# blinkenrocket_cr2032.net
KiCad netlist of a schematic drawn in EAGLE
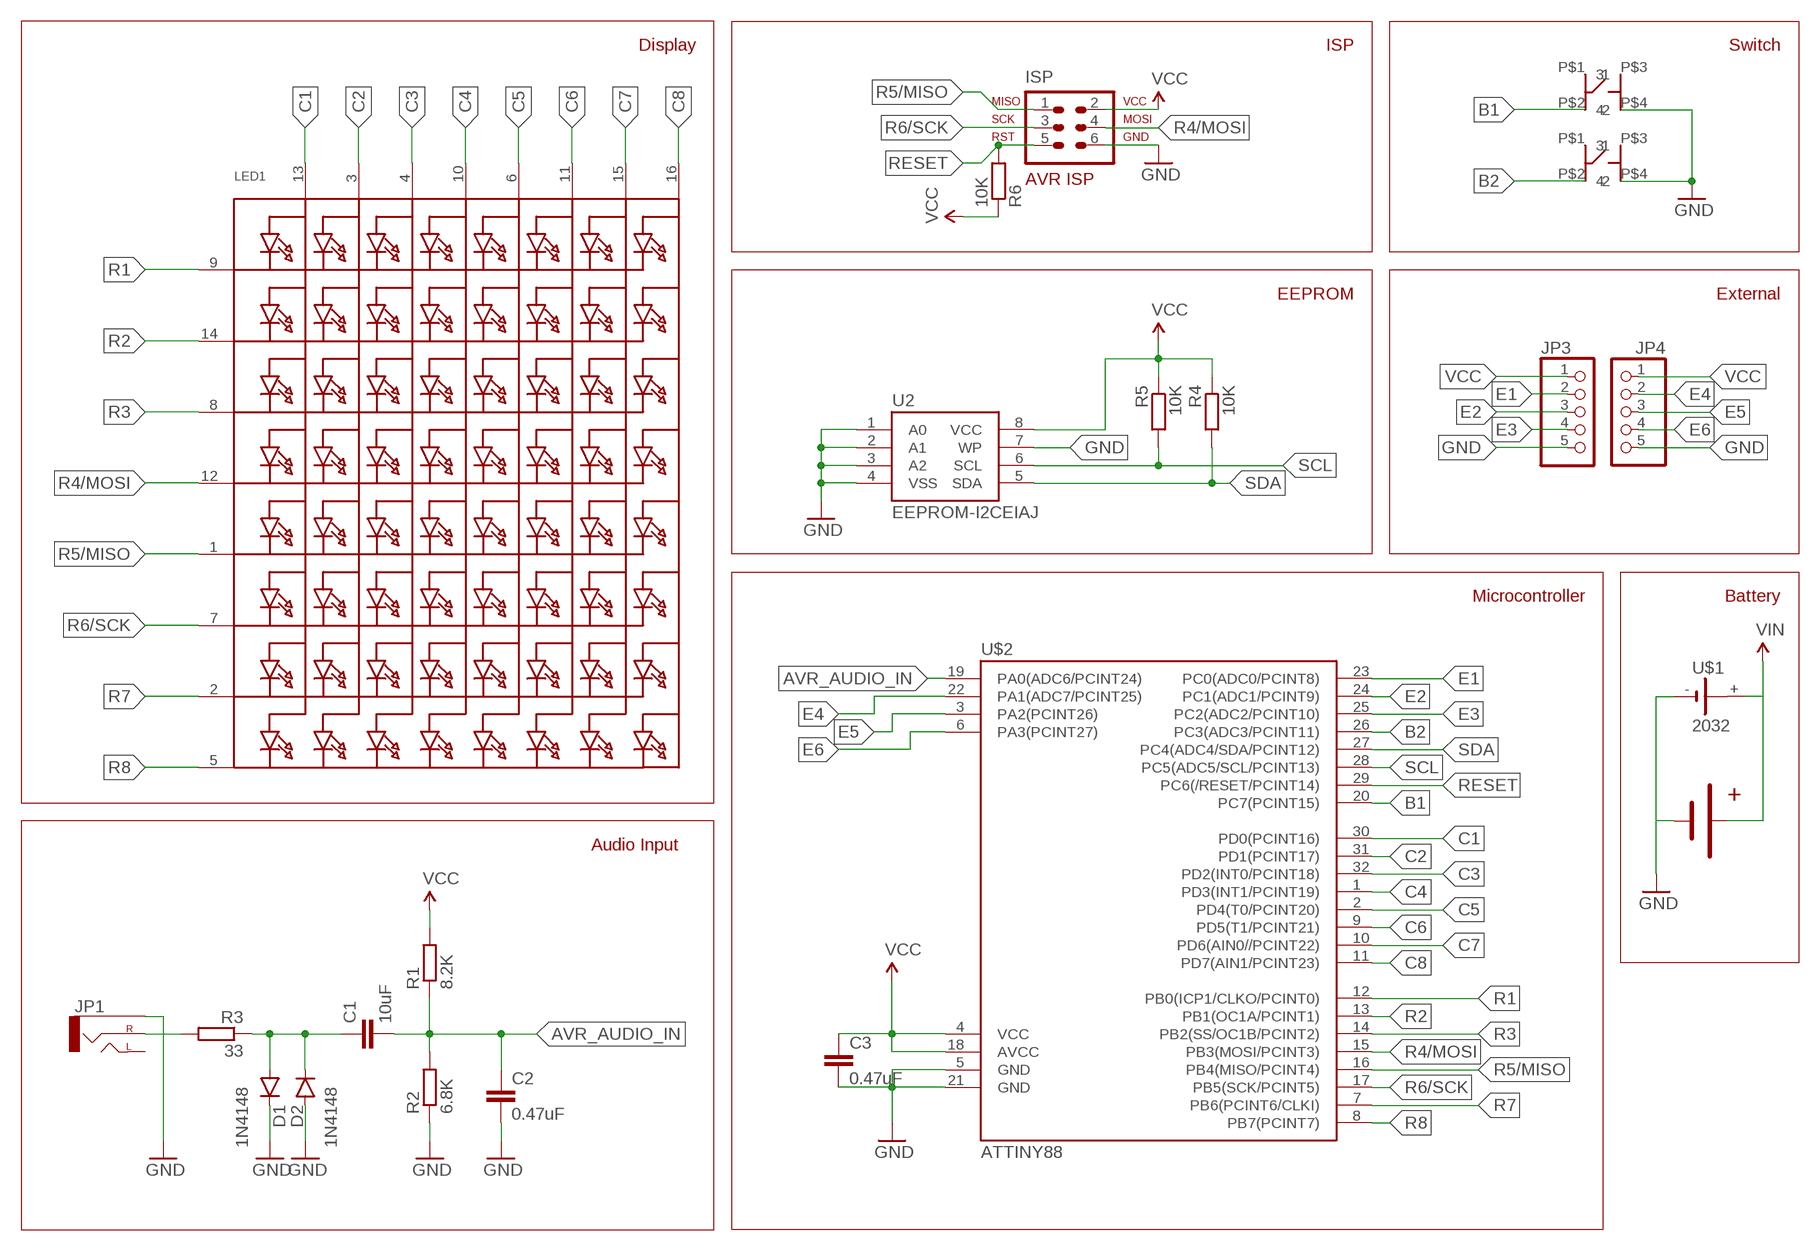
[diagram p0: schematic, sheet 1]

(export (version "E")
  (design (tool "Eeschema 10.0.6"))
  (components
    (comp (ref "C1")
      (value "10uF")
      (footprint "eagle-import:C0805K")
      (libsource (lib "eagle-import") (part "C-EUC0805K"))
    )
    (comp (ref "C2")
      (value "0.47uF")
      (footprint "eagle-import:C0805K")
      (libsource (lib "eagle-import") (part "C-EUC0805K"))
    )
    (comp (ref "C3")
      (value "0.47uF")
      (footprint "eagle-import:C0805K")
      (libsource (lib "eagle-import") (part "C-EUC0805K"))
    )
    (comp (ref "D1")
      (value "1N4148")
      (footprint "eagle-import:SOD-323")
      (libsource (lib "eagle-import") (part "DIODESOD"))
    )
    (comp (ref "D2")
      (value "1N4148")
      (footprint "eagle-import:SOD-323")
      (libsource (lib "eagle-import") (part "DIODESOD"))
    )
    (comp (ref "ISP")
      (value "AVR-ISP-6VERT")
      (footprint "eagle-import:AVR-ISP-6")
      (libsource (lib "eagle-import") (part "AVR-ISP-6VERT"))
    )
    (comp (ref "JP1")
      (value "AUDIO-JACKPTH")
      (footprint "eagle-import:AUDIO-JACK")
      (libsource (lib "eagle-import") (part "AUDIO-JACKPTH"))
    )
    (comp (ref "JP3")
      (value "PINHD-1X05_2.54-S")
      (footprint "eagle-import:1X05-S")
      (libsource (lib "eagle-import") (part "PINHD-1X05_2.54-S"))
    )
    (comp (ref "JP4")
      (value "PINHD-1X05_2.54-S")
      (footprint "eagle-import:1X05-S")
      (libsource (lib "eagle-import") (part "PINHD-1X05_2.54-S"))
    )
    (comp (ref "LED1")
      (value "SEGMENT_8X8_ROWCATHODEM12A881UR")
      (footprint "eagle-import:SEGMENT_BL-M12A881UR")
      (libsource (lib "eagle-import") (part "SEGMENT_8X8_ROWCATHODEM12A881UR"))
    )
    (comp (ref "R1")
      (value "8.2K")
      (footprint "eagle-import:M0805")
      (libsource (lib "eagle-import") (part "R-EU_M0805"))
    )
    (comp (ref "R2")
      (value "6.8K")
      (footprint "eagle-import:M0805")
      (libsource (lib "eagle-import") (part "R-EU_M0805"))
    )
    (comp (ref "R3")
      (value "33")
      (footprint "eagle-import:M0805")
      (libsource (lib "eagle-import") (part "R-EU_M0805"))
    )
    (comp (ref "R4")
      (value "10K")
      (footprint "eagle-import:M0805")
      (libsource (lib "eagle-import") (part "R-EU_M0805"))
    )
    (comp (ref "R5")
      (value "10K")
      (footprint "eagle-import:M0805")
      (libsource (lib "eagle-import") (part "R-EU_M0805"))
    )
    (comp (ref "R6")
      (value "10K")
      (footprint "eagle-import:M0805")
      (libsource (lib "eagle-import") (part "R-EU_M0805"))
    )
    (comp (ref "SW1")
      (value "SWITCH-4POMRON-6-6-SWITCH")
      (footprint "eagle-import:4P-OMRON-6-6-SWITCH")
      (libsource (lib "eagle-import") (part "SWITCH-4POMRON-6-6-SWITCH"))
    )
    (comp (ref "SW2")
      (value "SWITCH-4POMRON-6-6-SWITCH")
      (footprint "eagle-import:4P-OMRON-6-6-SWITCH")
      (libsource (lib "eagle-import") (part "SWITCH-4POMRON-6-6-SWITCH"))
    )
    (comp (ref "U$1")
      (value "2032")
      (footprint "eagle-import:KZH20SMD")
      (libsource (lib "eagle-import") (part "2032"))
    )
    (comp (ref "U$2")
      (value "ATTINY88")
      (footprint "eagle-import:TQFP32-08")
      (libsource (lib "eagle-import") (part "TINY48/88B"))
    )
    (comp (ref "U$3")
      (value "BATTERYPAD")
      (footprint "eagle-import:BATTERYPAD")
      (libsource (lib "eagle-import") (part "BATTERYPAD"))
    )
    (comp (ref "U2")
      (value "EEPROM-I2CEIAJ")
      (footprint "eagle-import:SO08-EIAJ")
      (libsource (lib "eagle-import") (part "EEPROM-I2CEIAJ"))
    )
  )
  (nets
    (net (code "1") (name "AVR_AUDIO_IN") (class "Default")
      (node (ref "C1") (pin "2") (pinfunction "2_2") (pintype "passive"))
      (node (ref "C2") (pin "1") (pinfunction "1_1") (pintype "passive"))
      (node (ref "R1") (pin "1") (pinfunction "1_1") (pintype "passive"))
      (node (ref "R2") (pin "2") (pinfunction "2_2") (pintype "passive"))
      (node (ref "U$2") (pin "19") (pinfunction "PA0(ADC6/PCINT24)_19") (pintype "bidirectional"))
    )
    (net (code "2") (name "B1") (class "Default")
      (node (ref "SW2") (pin "P$2") (pinfunction "2_P$2") (pintype "bidirectional"))
      (node (ref "U$2") (pin "20") (pinfunction "PC7(PCINT15)_20") (pintype "bidirectional"))
    )
    (net (code "3") (name "B2") (class "Default")
      (node (ref "SW1") (pin "P$2") (pinfunction "2_P$2") (pintype "bidirectional"))
      (node (ref "U$2") (pin "26") (pinfunction "PC3(ADC3/PCINT11)_26") (pintype "bidirectional"))
    )
    (net (code "4") (name "C1") (class "Default")
      (node (ref "LED1") (pin "13") (pinfunction "A1_13") (pintype "bidirectional"))
      (node (ref "U$2") (pin "30") (pinfunction "PD0(PCINT16)_30") (pintype "bidirectional"))
    )
    (net (code "5") (name "C2") (class "Default")
      (node (ref "LED1") (pin "3") (pinfunction "A2_3") (pintype "bidirectional"))
      (node (ref "U$2") (pin "31") (pinfunction "PD1(PCINT17)_31") (pintype "bidirectional"))
    )
    (net (code "6") (name "C3") (class "Default")
      (node (ref "LED1") (pin "4") (pinfunction "A3_4") (pintype "bidirectional"))
      (node (ref "U$2") (pin "32") (pinfunction "PD2(INT0/PCINT18)_32") (pintype "bidirectional"))
    )
    (net (code "7") (name "C4") (class "Default")
      (node (ref "LED1") (pin "10") (pinfunction "A4_10") (pintype "bidirectional"))
      (node (ref "U$2") (pin "1") (pinfunction "PD3(INT1/PCINT19)_1") (pintype "bidirectional"))
    )
    (net (code "8") (name "C5") (class "Default")
      (node (ref "LED1") (pin "6") (pinfunction "A5_6") (pintype "bidirectional"))
      (node (ref "U$2") (pin "2") (pinfunction "PD4(T0/PCINT20)_2") (pintype "bidirectional"))
    )
    (net (code "9") (name "C6") (class "Default")
      (node (ref "LED1") (pin "11") (pinfunction "A6_11") (pintype "bidirectional"))
      (node (ref "U$2") (pin "9") (pinfunction "PD5(T1/PCINT21)_9") (pintype "bidirectional"))
    )
    (net (code "10") (name "C7") (class "Default")
      (node (ref "LED1") (pin "15") (pinfunction "A7_15") (pintype "bidirectional"))
      (node (ref "U$2") (pin "10") (pinfunction "PD6(AIN0//PCINT22)_10") (pintype "bidirectional"))
    )
    (net (code "11") (name "C8") (class "Default")
      (node (ref "LED1") (pin "16") (pinfunction "A8_16") (pintype "bidirectional"))
      (node (ref "U$2") (pin "11") (pinfunction "PD7(AIN1/PCINT23)_11") (pintype "bidirectional"))
    )
    (net (code "12") (name "E1") (class "Default")
      (node (ref "JP3") (pin "2") (pinfunction "2_2") (pintype "passive"))
      (node (ref "U$2") (pin "23") (pinfunction "PC0(ADC0/PCINT8)_23") (pintype "bidirectional"))
    )
    (net (code "13") (name "E2") (class "Default")
      (node (ref "JP3") (pin "3") (pinfunction "3_3") (pintype "passive"))
      (node (ref "U$2") (pin "24") (pinfunction "PC1(ADC1/PCINT9)_24") (pintype "bidirectional"))
    )
    (net (code "14") (name "E3") (class "Default")
      (node (ref "JP3") (pin "4") (pinfunction "4_4") (pintype "passive"))
      (node (ref "U$2") (pin "25") (pinfunction "PC2(ADC2/PCINT10)_25") (pintype "bidirectional"))
    )
    (net (code "15") (name "E4") (class "Default")
      (node (ref "JP4") (pin "2") (pinfunction "2_2") (pintype "passive"))
      (node (ref "U$2") (pin "22") (pinfunction "PA1(ADC7/PCINT25)_22") (pintype "bidirectional"))
    )
    (net (code "16") (name "E5") (class "Default")
      (node (ref "JP4") (pin "3") (pinfunction "3_3") (pintype "passive"))
      (node (ref "U$2") (pin "3") (pinfunction "PA2(PCINT26)_3") (pintype "bidirectional"))
    )
    (net (code "17") (name "E6") (class "Default")
      (node (ref "JP4") (pin "4") (pinfunction "4_4") (pintype "passive"))
      (node (ref "U$2") (pin "6") (pinfunction "PA3(PCINT27)_6") (pintype "bidirectional"))
    )
    (net (code "18") (name "GND") (class "Default")
      (node (ref "C2") (pin "2") (pinfunction "2_2") (pintype "passive"))
      (node (ref "C3") (pin "2") (pinfunction "2_2") (pintype "passive"))
      (node (ref "D1") (pin "C") (pinfunction "C_C") (pintype "passive"))
      (node (ref "D2") (pin "A") (pinfunction "A_A") (pintype "passive"))
      (node (ref "ISP") (pin "6") (pinfunction "6_6") (pintype "passive"))
      (node (ref "JP1") (pin "SLEEVE") (pinfunction "SLEEVE_SLEEVE") (pintype "bidirectional"))
      (node (ref "JP3") (pin "5") (pinfunction "5_5") (pintype "passive"))
      (node (ref "JP4") (pin "5") (pinfunction "5_5") (pintype "passive"))
      (node (ref "R2") (pin "1") (pinfunction "1_1") (pintype "passive"))
      (node (ref "SW1") (pin "P$4") (pinfunction "4_P$4") (pintype "bidirectional"))
      (node (ref "SW2") (pin "P$4") (pinfunction "4_P$4") (pintype "bidirectional"))
      (node (ref "U$1") (pin "-") (pinfunction "-_-") (pintype "passive"))
      (node (ref "U$2") (pin "21") (pinfunction "GND_21") (pintype "power_in"))
      (node (ref "U$2") (pin "5") (pinfunction "GND_5") (pintype "power_in"))
      (node (ref "U$3") (pin "-VE") (pinfunction "-VE_-VE") (pintype "power_in"))
      (node (ref "U2") (pin "1") (pinfunction "A0_1") (pintype "bidirectional"))
      (node (ref "U2") (pin "2") (pinfunction "A1_2") (pintype "bidirectional"))
      (node (ref "U2") (pin "3") (pinfunction "A2_3") (pintype "bidirectional"))
      (node (ref "U2") (pin "4") (pinfunction "VSS_4") (pintype "power_in"))
      (node (ref "U2") (pin "7") (pinfunction "WP_7") (pintype "bidirectional"))
    )
    (net (code "19") (name "Net-(C1-Pad1)") (class "Default")
      (node (ref "C1") (pin "1") (pinfunction "1_1") (pintype "passive"))
      (node (ref "D1") (pin "A") (pinfunction "A_A") (pintype "passive"))
      (node (ref "D2") (pin "C") (pinfunction "C_C") (pintype "passive"))
      (node (ref "R3") (pin "1") (pinfunction "1_1") (pintype "passive"))
    )
    (net (code "20") (name "Net-(JP1-RIGHT)") (class "Default")
      (node (ref "JP1") (pin "RING") (pinfunction "RIGHT_RING") (pintype "bidirectional"))
      (node (ref "R3") (pin "2") (pinfunction "2_2") (pintype "passive"))
    )
    (net (code "21") (name "R1") (class "Default")
      (node (ref "LED1") (pin "9") (pinfunction "K1_9") (pintype "bidirectional"))
      (node (ref "U$2") (pin "12") (pinfunction "PB0(ICP1/CLKO/PCINT0)_12") (pintype "bidirectional"))
    )
    (net (code "22") (name "R2") (class "Default")
      (node (ref "LED1") (pin "14") (pinfunction "K2_14") (pintype "bidirectional"))
      (node (ref "U$2") (pin "13") (pinfunction "PB1(OC1A/PCINT1)_13") (pintype "bidirectional"))
    )
    (net (code "23") (name "R3") (class "Default")
      (node (ref "LED1") (pin "8") (pinfunction "K3_8") (pintype "bidirectional"))
      (node (ref "U$2") (pin "14") (pinfunction "PB2(SS/OC1B/PCINT2)_14") (pintype "bidirectional"))
    )
    (net (code "24") (name "R4{slash}MOSI") (class "Default")
      (node (ref "ISP") (pin "4") (pinfunction "4_4") (pintype "passive"))
      (node (ref "LED1") (pin "12") (pinfunction "K4_12") (pintype "bidirectional"))
      (node (ref "U$2") (pin "15") (pinfunction "PB3(MOSI/PCINT3)_15") (pintype "bidirectional"))
    )
    (net (code "25") (name "R5{slash}MISO") (class "Default")
      (node (ref "ISP") (pin "1") (pinfunction "1_1") (pintype "passive"))
      (node (ref "LED1") (pin "1") (pinfunction "K5_1") (pintype "bidirectional"))
      (node (ref "U$2") (pin "16") (pinfunction "PB4(MISO/PCINT4)_16") (pintype "bidirectional"))
    )
    (net (code "26") (name "R6{slash}SCK") (class "Default")
      (node (ref "ISP") (pin "3") (pinfunction "3_3") (pintype "passive"))
      (node (ref "LED1") (pin "7") (pinfunction "K6_7") (pintype "bidirectional"))
      (node (ref "U$2") (pin "17") (pinfunction "PB5(SCK/PCINT5)_17") (pintype "bidirectional"))
    )
    (net (code "27") (name "R7") (class "Default")
      (node (ref "LED1") (pin "2") (pinfunction "K7_2") (pintype "bidirectional"))
      (node (ref "U$2") (pin "7") (pinfunction "PB6(PCINT6/CLKI)_7") (pintype "bidirectional"))
    )
    (net (code "28") (name "R8") (class "Default")
      (node (ref "LED1") (pin "5") (pinfunction "K8_5") (pintype "bidirectional"))
      (node (ref "U$2") (pin "8") (pinfunction "PB7(PCINT7)_8") (pintype "bidirectional"))
    )
    (net (code "29") (name "RESET") (class "Default")
      (node (ref "ISP") (pin "5") (pinfunction "5_5") (pintype "passive"))
      (node (ref "R6") (pin "2") (pinfunction "2_2") (pintype "passive"))
      (node (ref "U$2") (pin "29") (pinfunction "PC6(/RESET/PCINT14)_29") (pintype "bidirectional"))
    )
    (net (code "30") (name "SCL") (class "Default")
      (node (ref "R5") (pin "2") (pinfunction "2_2") (pintype "passive"))
      (node (ref "U$2") (pin "28") (pinfunction "PC5(ADC5/SCL/PCINT13)_28") (pintype "bidirectional"))
      (node (ref "U2") (pin "6") (pinfunction "SCL_6") (pintype "bidirectional"))
    )
    (net (code "31") (name "SDA") (class "Default")
      (node (ref "R4") (pin "2") (pinfunction "2_2") (pintype "passive"))
      (node (ref "U$2") (pin "27") (pinfunction "PC4(ADC4/SDA/PCINT12)_27") (pintype "bidirectional"))
      (node (ref "U2") (pin "5") (pinfunction "SDA_5") (pintype "bidirectional"))
    )
    (net (code "32") (name "VCC") (class "Default")
      (node (ref "C3") (pin "1") (pinfunction "1_1") (pintype "passive"))
      (node (ref "ISP") (pin "2") (pinfunction "2_2") (pintype "passive"))
      (node (ref "JP3") (pin "1") (pinfunction "1_1") (pintype "passive"))
      (node (ref "JP4") (pin "1") (pinfunction "1_1") (pintype "passive"))
      (node (ref "R1") (pin "2") (pinfunction "2_2") (pintype "passive"))
      (node (ref "R4") (pin "1") (pinfunction "1_1") (pintype "passive"))
      (node (ref "R5") (pin "1") (pinfunction "1_1") (pintype "passive"))
      (node (ref "R6") (pin "1") (pinfunction "1_1") (pintype "passive"))
      (node (ref "U$1") (pin "+") (pinfunction "+_+") (pintype "passive"))
      (node (ref "U$2") (pin "18") (pinfunction "AVCC_18") (pintype "passive"))
      (node (ref "U$2") (pin "4") (pinfunction "VCC_4") (pintype "power_in"))
      (node (ref "U$3") (pin "+VE") (pinfunction "+VE_+VE") (pintype "power_in"))
      (node (ref "U2") (pin "8") (pinfunction "VCC_8") (pintype "power_in"))
    )
    (net (code "33") (name "unconnected-(JP1-LEFT-PadTIP)") (class "Default")
      (node (ref "JP1") (pin "TIP") (pinfunction "LEFT_TIP") (pintype "bidirectional"))
    )
    (net (code "34") (name "unconnected-(SW1-1-PadP$1)") (class "Default")
      (node (ref "SW1") (pin "P$1") (pinfunction "1_P$1") (pintype "bidirectional"))
    )
    (net (code "35") (name "unconnected-(SW1-3-PadP$3)") (class "Default")
      (node (ref "SW1") (pin "P$3") (pinfunction "3_P$3") (pintype "bidirectional"))
    )
    (net (code "36") (name "unconnected-(SW2-1-PadP$1)") (class "Default")
      (node (ref "SW2") (pin "P$1") (pinfunction "1_P$1") (pintype "bidirectional"))
    )
    (net (code "37") (name "unconnected-(SW2-3-PadP$3)") (class "Default")
      (node (ref "SW2") (pin "P$3") (pinfunction "3_P$3") (pintype "bidirectional"))
    )
  )
)
